# sensor_board.net
KiCad netlist of a schematic drawn in EAGLE
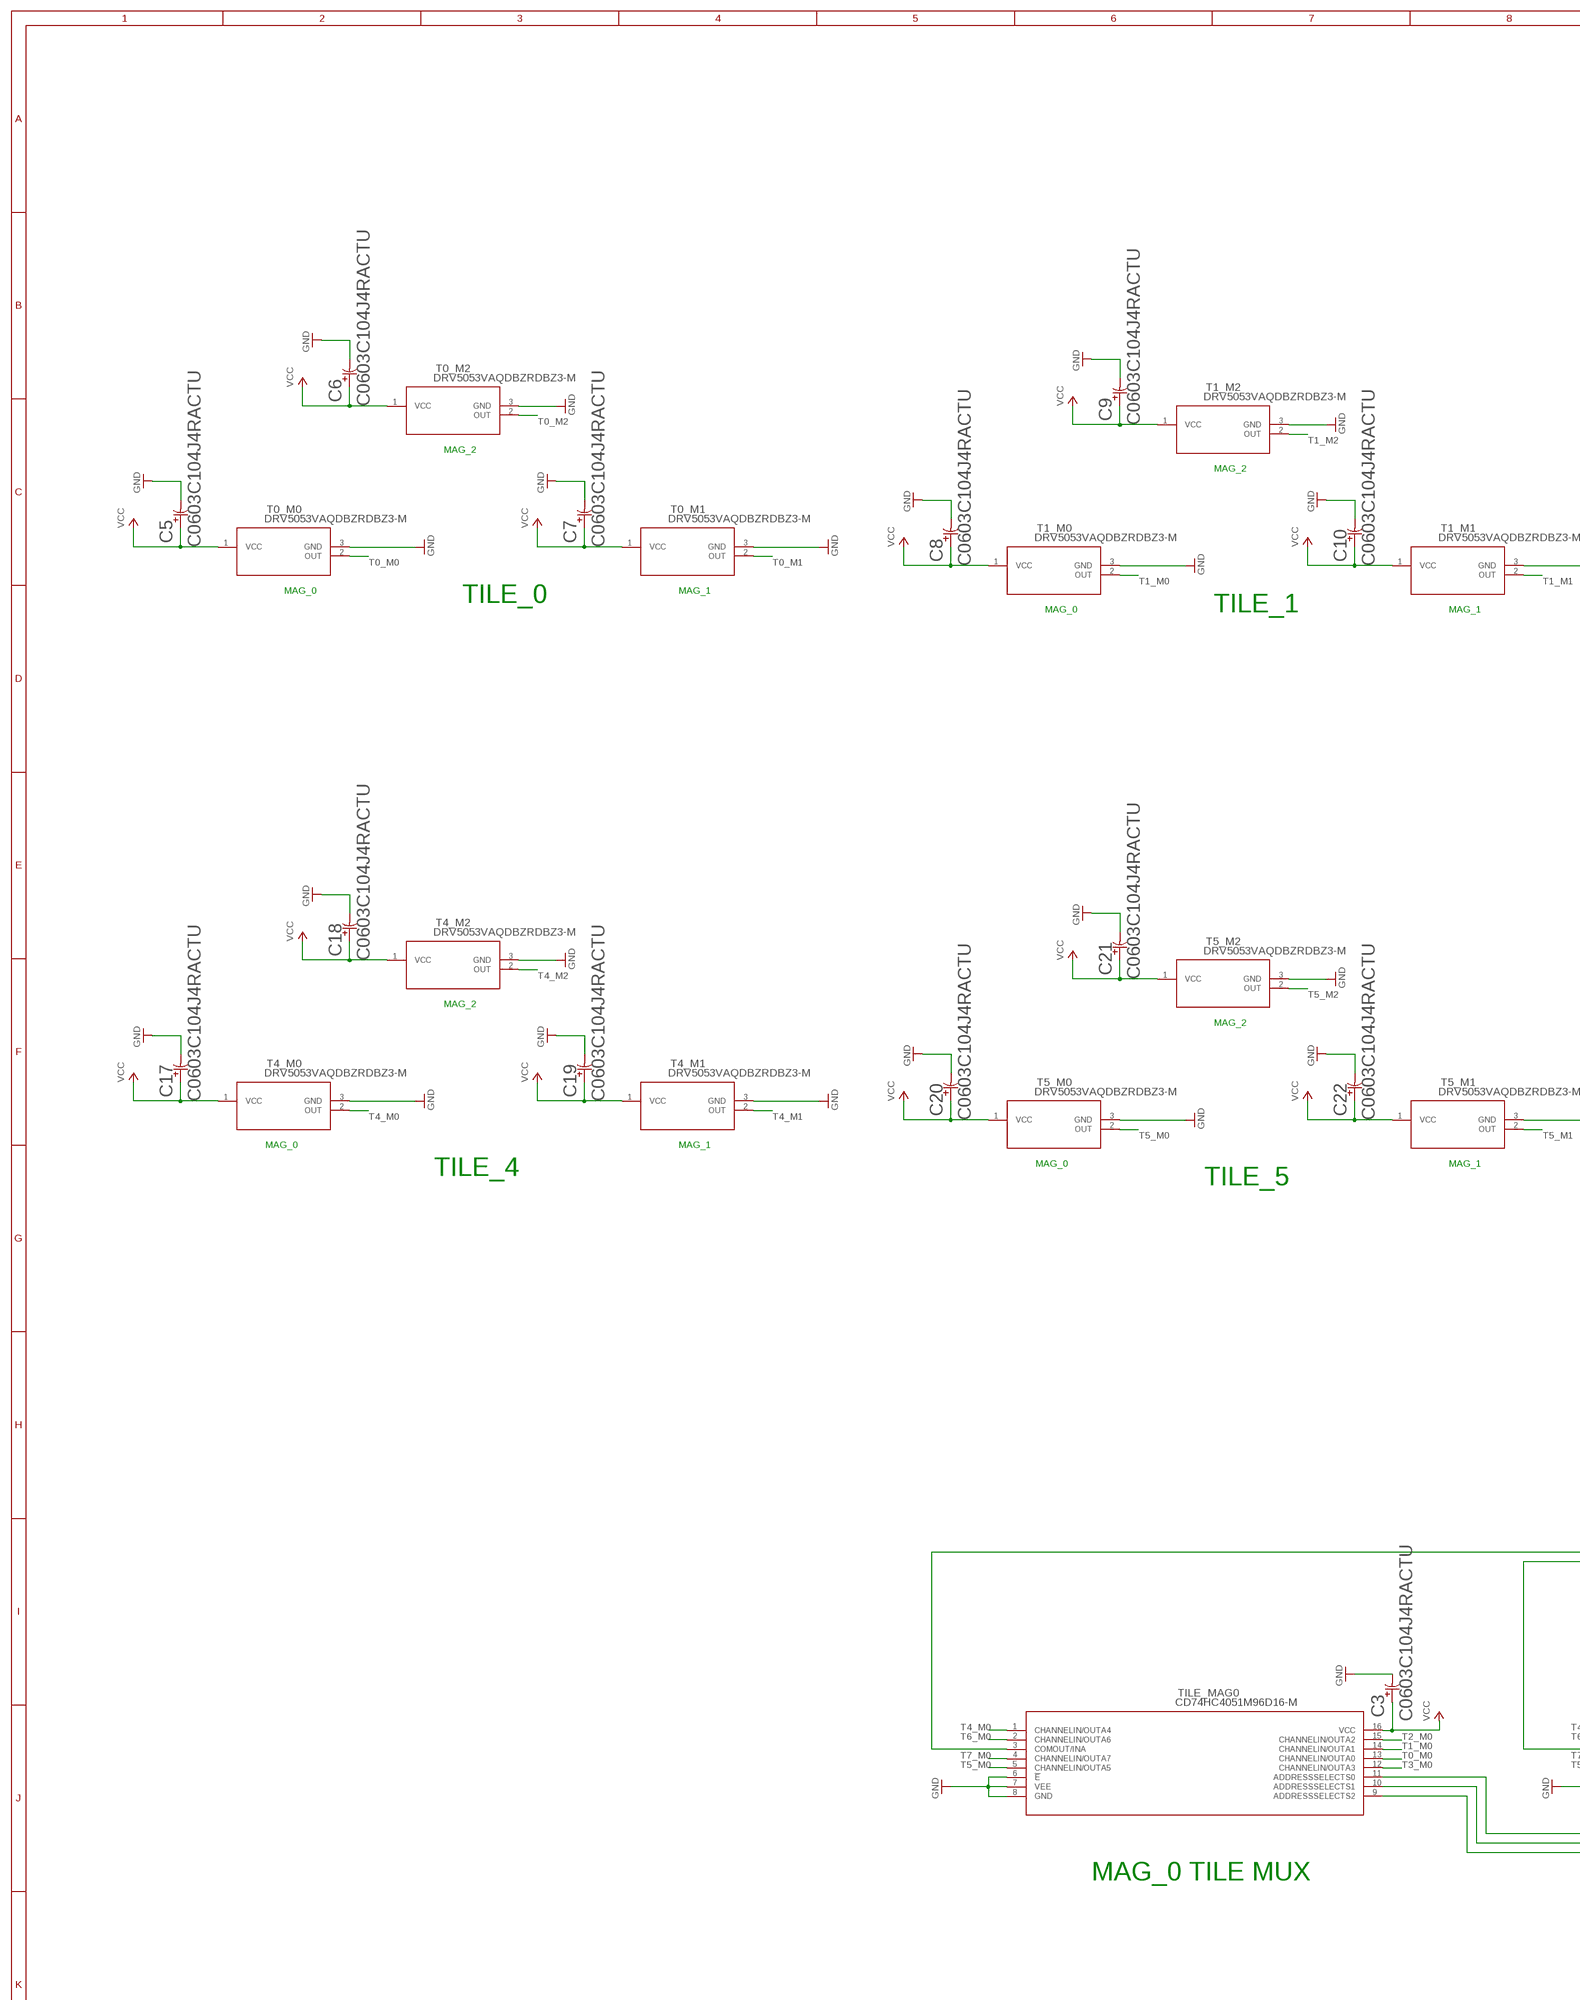
[diagram p0: schematic, sheet 1, part 1 of 3]
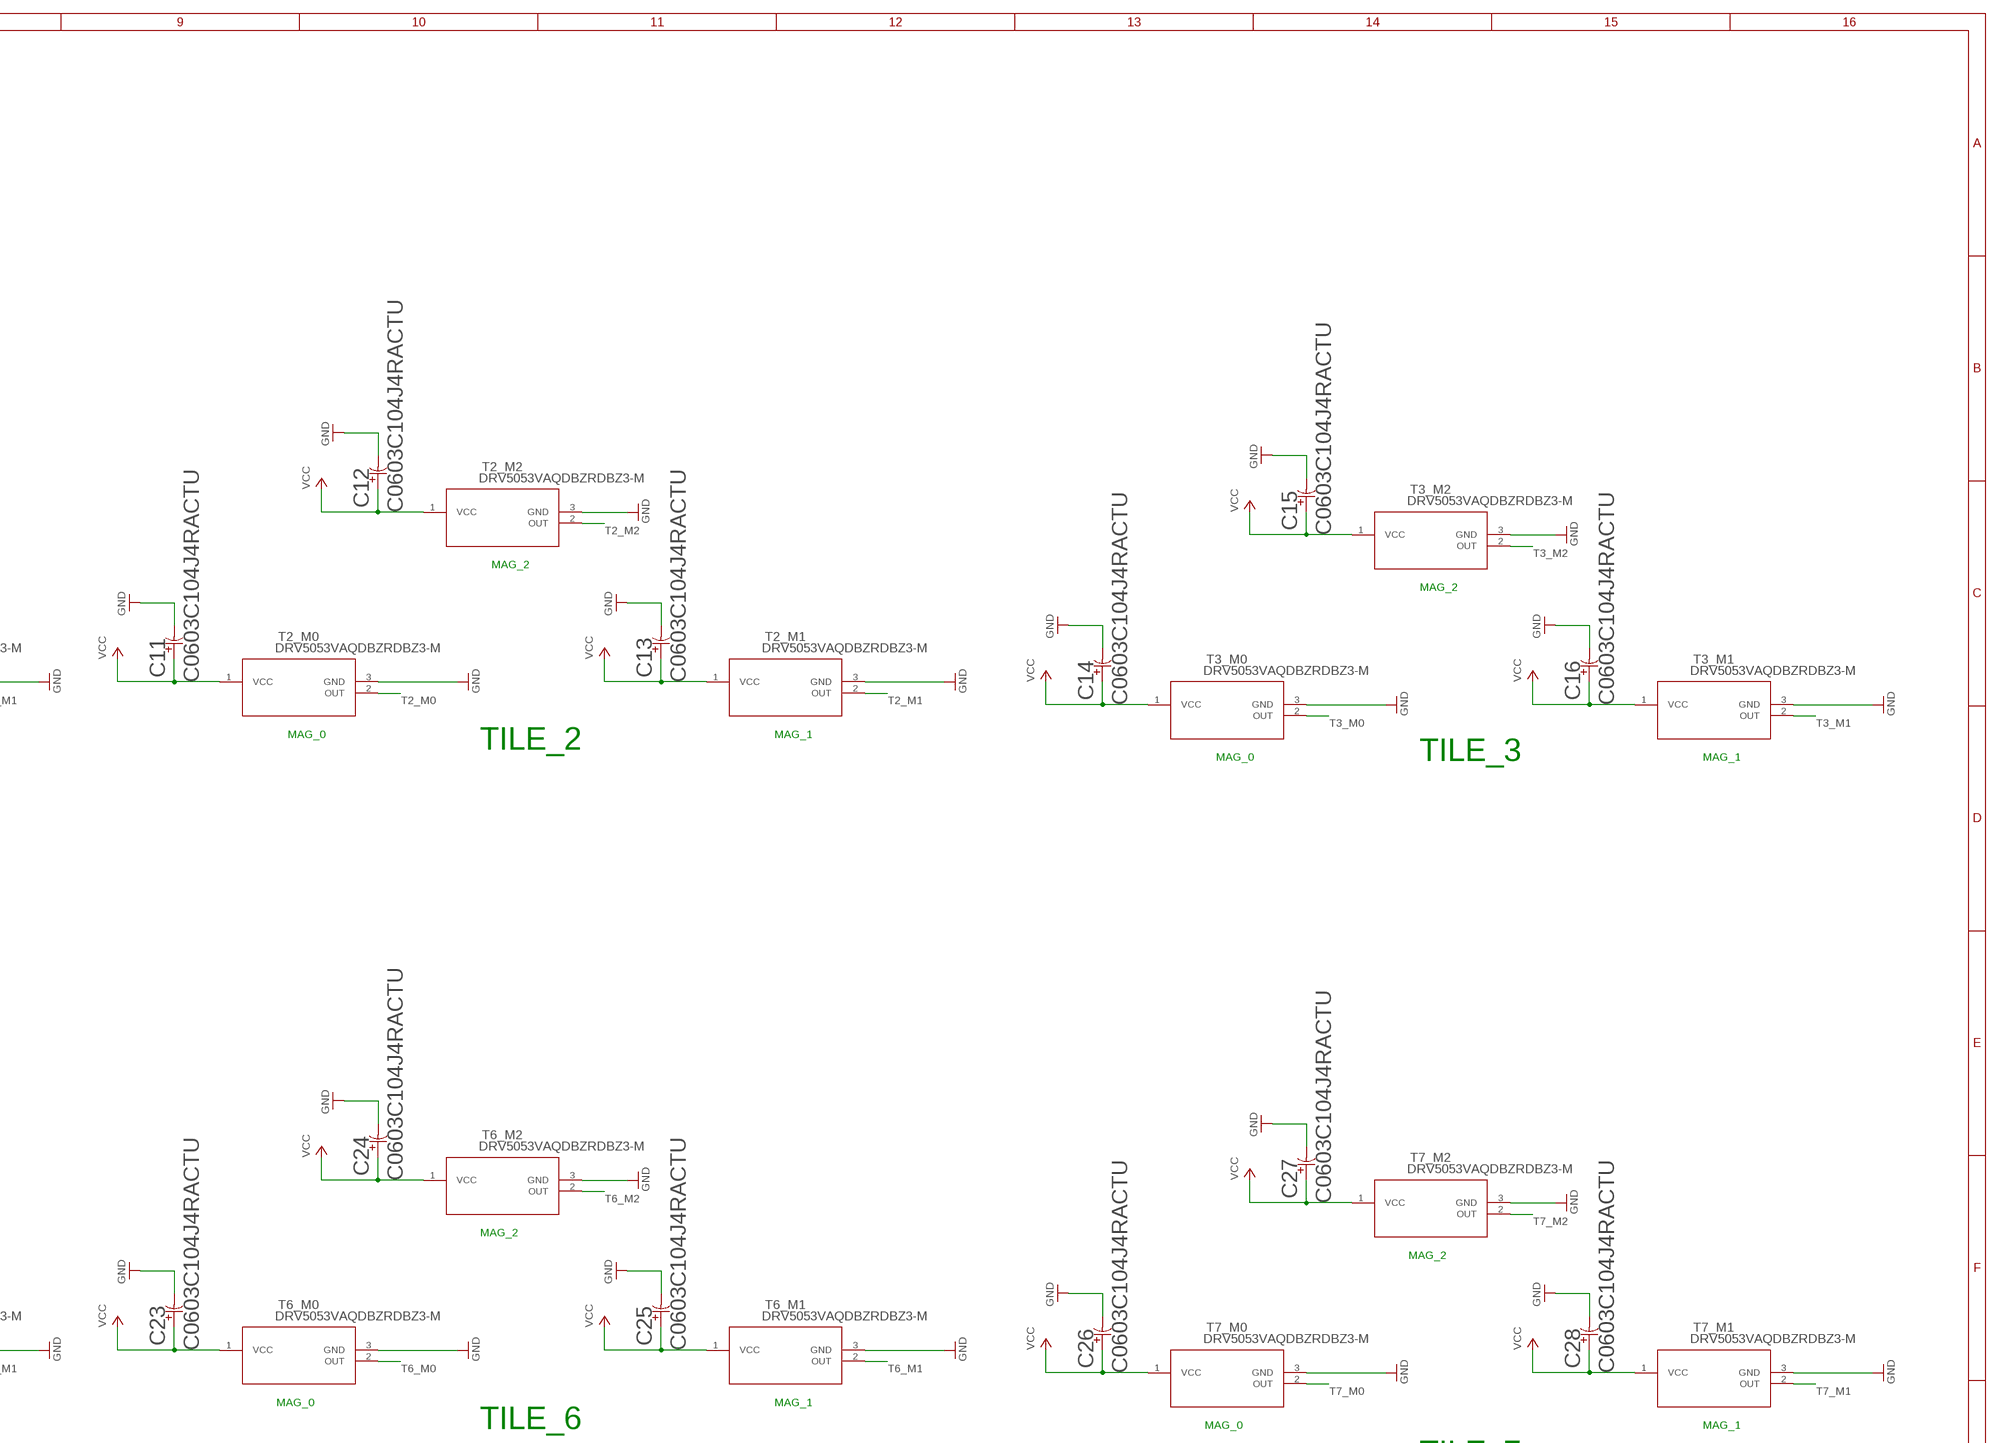
[diagram p1: schematic, sheet 1, part 2 of 3]
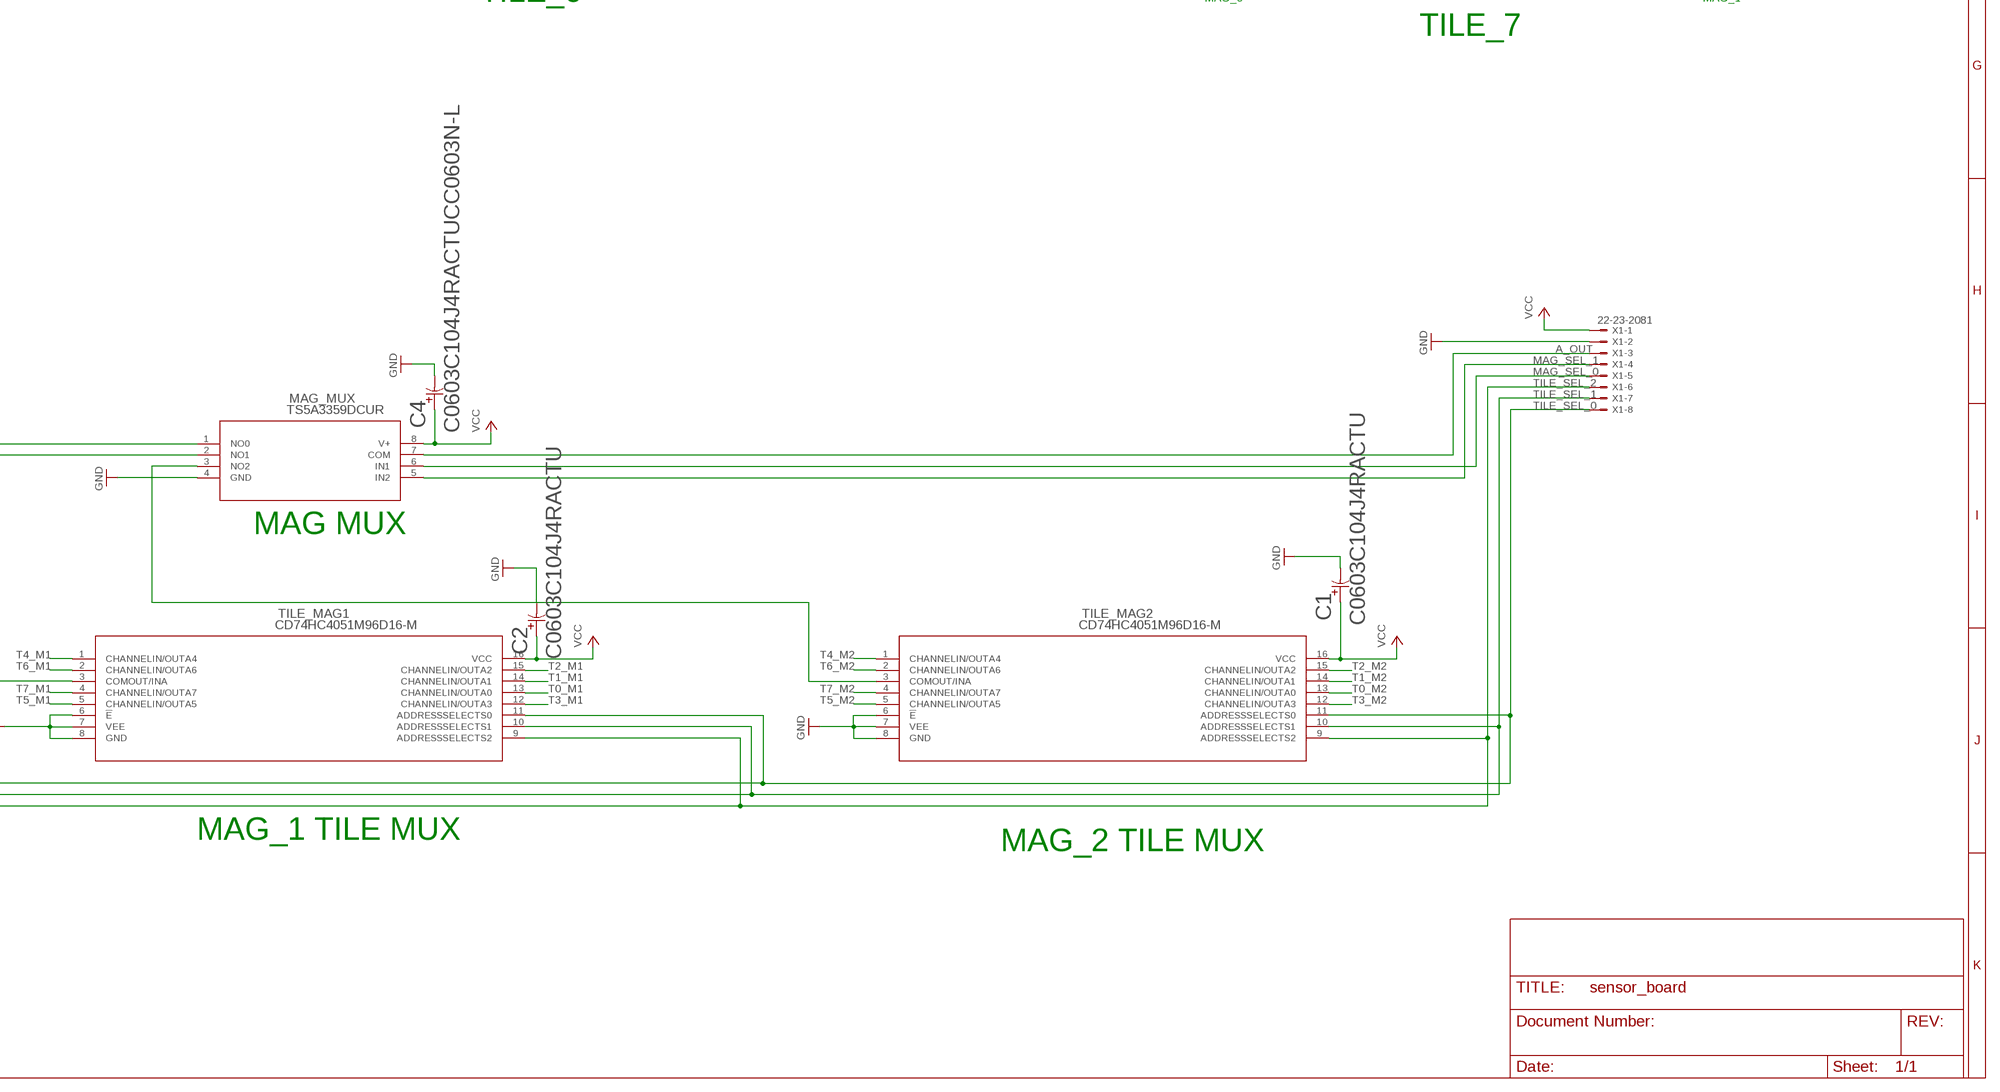
[diagram p2: schematic, sheet 1, part 3 of 3]

(export (version "E")
  (design (tool "Eeschema 10.0.6"))
  (components
    (comp (ref "C1")
      (value "C0603C104J4RACTU")
      (footprint "eagle-import:CC0603N")
      (libsource (lib "eagle-import") (part "C0603C104J4RACTU"))
    )
    (comp (ref "C2")
      (value "C0603C104J4RACTU")
      (footprint "eagle-import:CC0603N")
      (libsource (lib "eagle-import") (part "C0603C104J4RACTU"))
    )
    (comp (ref "C3")
      (value "C0603C104J4RACTU")
      (footprint "eagle-import:CC0603N")
      (libsource (lib "eagle-import") (part "C0603C104J4RACTU"))
    )
    (comp (ref "C4")
      (value "C0603C104J4RACTUCC0603N-L")
      (footprint "eagle-import:CC0603N-L")
      (fields (field (name "MANUFACTURER_PART_NUMBER") "C0603C104J4RACTU"))
      (libsource (lib "eagle-import") (part "C0603C104J4RACTUCC0603N-L"))
    )
    (comp (ref "C5")
      (value "C0603C104J4RACTU")
      (footprint "eagle-import:CC0603N")
      (libsource (lib "eagle-import") (part "C0603C104J4RACTU"))
    )
    (comp (ref "C6")
      (value "C0603C104J4RACTU")
      (footprint "eagle-import:CC0603N")
      (libsource (lib "eagle-import") (part "C0603C104J4RACTU"))
    )
    (comp (ref "C7")
      (value "C0603C104J4RACTU")
      (footprint "eagle-import:CC0603N")
      (libsource (lib "eagle-import") (part "C0603C104J4RACTU"))
    )
    (comp (ref "C8")
      (value "C0603C104J4RACTU")
      (footprint "eagle-import:CC0603N")
      (libsource (lib "eagle-import") (part "C0603C104J4RACTU"))
    )
    (comp (ref "C9")
      (value "C0603C104J4RACTU")
      (footprint "eagle-import:CC0603N")
      (libsource (lib "eagle-import") (part "C0603C104J4RACTU"))
    )
    (comp (ref "C10")
      (value "C0603C104J4RACTU")
      (footprint "eagle-import:CC0603N")
      (libsource (lib "eagle-import") (part "C0603C104J4RACTU"))
    )
    (comp (ref "C11")
      (value "C0603C104J4RACTU")
      (footprint "eagle-import:CC0603N")
      (libsource (lib "eagle-import") (part "C0603C104J4RACTU"))
    )
    (comp (ref "C12")
      (value "C0603C104J4RACTU")
      (footprint "eagle-import:CC0603N")
      (libsource (lib "eagle-import") (part "C0603C104J4RACTU"))
    )
    (comp (ref "C13")
      (value "C0603C104J4RACTU")
      (footprint "eagle-import:CC0603N")
      (libsource (lib "eagle-import") (part "C0603C104J4RACTU"))
    )
    (comp (ref "C14")
      (value "C0603C104J4RACTU")
      (footprint "eagle-import:CC0603N")
      (libsource (lib "eagle-import") (part "C0603C104J4RACTU"))
    )
    (comp (ref "C15")
      (value "C0603C104J4RACTU")
      (footprint "eagle-import:CC0603N")
      (libsource (lib "eagle-import") (part "C0603C104J4RACTU"))
    )
    (comp (ref "C16")
      (value "C0603C104J4RACTU")
      (footprint "eagle-import:CC0603N")
      (libsource (lib "eagle-import") (part "C0603C104J4RACTU"))
    )
    (comp (ref "C17")
      (value "C0603C104J4RACTU")
      (footprint "eagle-import:CC0603N")
      (libsource (lib "eagle-import") (part "C0603C104J4RACTU"))
    )
    (comp (ref "C18")
      (value "C0603C104J4RACTU")
      (footprint "eagle-import:CC0603N")
      (libsource (lib "eagle-import") (part "C0603C104J4RACTU"))
    )
    (comp (ref "C19")
      (value "C0603C104J4RACTU")
      (footprint "eagle-import:CC0603N")
      (libsource (lib "eagle-import") (part "C0603C104J4RACTU"))
    )
    (comp (ref "C20")
      (value "C0603C104J4RACTU")
      (footprint "eagle-import:CC0603N")
      (libsource (lib "eagle-import") (part "C0603C104J4RACTU"))
    )
    (comp (ref "C21")
      (value "C0603C104J4RACTU")
      (footprint "eagle-import:CC0603N")
      (libsource (lib "eagle-import") (part "C0603C104J4RACTU"))
    )
    (comp (ref "C22")
      (value "C0603C104J4RACTU")
      (footprint "eagle-import:CC0603N")
      (libsource (lib "eagle-import") (part "C0603C104J4RACTU"))
    )
    (comp (ref "C23")
      (value "C0603C104J4RACTU")
      (footprint "eagle-import:CC0603N")
      (libsource (lib "eagle-import") (part "C0603C104J4RACTU"))
    )
    (comp (ref "C24")
      (value "C0603C104J4RACTU")
      (footprint "eagle-import:CC0603N")
      (libsource (lib "eagle-import") (part "C0603C104J4RACTU"))
    )
    (comp (ref "C25")
      (value "C0603C104J4RACTU")
      (footprint "eagle-import:CC0603N")
      (libsource (lib "eagle-import") (part "C0603C104J4RACTU"))
    )
    (comp (ref "C26")
      (value "C0603C104J4RACTU")
      (footprint "eagle-import:CC0603N")
      (libsource (lib "eagle-import") (part "C0603C104J4RACTU"))
    )
    (comp (ref "C27")
      (value "C0603C104J4RACTU")
      (footprint "eagle-import:CC0603N")
      (libsource (lib "eagle-import") (part "C0603C104J4RACTU"))
    )
    (comp (ref "C28")
      (value "C0603C104J4RACTU")
      (footprint "eagle-import:CC0603N")
      (libsource (lib "eagle-import") (part "C0603C104J4RACTU"))
    )
    (comp (ref "MAG_MUX")
      (value "TS5A3359DCUR")
      (footprint "eagle-import:DCU8")
      (libsource (lib "eagle-import") (part "TS5A3359DCUR"))
    )
    (comp (ref "T0_M0")
      (value "DRV5053VAQDBZRDBZ3-M")
      (footprint "eagle-import:DBZ3-M")
      (fields (field (name "MANUFACTURER_PART_NUMBER") "drv5053vaqdbzr"))
      (libsource (lib "eagle-import") (part "DRV5053VAQDBZRDBZ3-M"))
    )
    (comp (ref "T0_M1")
      (value "DRV5053VAQDBZRDBZ3-M")
      (footprint "eagle-import:DBZ3-M")
      (fields (field (name "MANUFACTURER_PART_NUMBER") "drv5053vaqdbzr"))
      (libsource (lib "eagle-import") (part "DRV5053VAQDBZRDBZ3-M"))
    )
    (comp (ref "T0_M2")
      (value "DRV5053VAQDBZRDBZ3-M")
      (footprint "eagle-import:DBZ3-M")
      (fields (field (name "MANUFACTURER_PART_NUMBER") "drv5053vaqdbzr"))
      (libsource (lib "eagle-import") (part "DRV5053VAQDBZRDBZ3-M"))
    )
    (comp (ref "T1_M0")
      (value "DRV5053VAQDBZRDBZ3-M")
      (footprint "eagle-import:DBZ3-M")
      (fields (field (name "MANUFACTURER_PART_NUMBER") "drv5053vaqdbzr"))
      (libsource (lib "eagle-import") (part "DRV5053VAQDBZRDBZ3-M"))
    )
    (comp (ref "T1_M1")
      (value "DRV5053VAQDBZRDBZ3-M")
      (footprint "eagle-import:DBZ3-M")
      (fields (field (name "MANUFACTURER_PART_NUMBER") "drv5053vaqdbzr"))
      (libsource (lib "eagle-import") (part "DRV5053VAQDBZRDBZ3-M"))
    )
    (comp (ref "T1_M2")
      (value "DRV5053VAQDBZRDBZ3-M")
      (footprint "eagle-import:DBZ3-M")
      (fields (field (name "MANUFACTURER_PART_NUMBER") "drv5053vaqdbzr"))
      (libsource (lib "eagle-import") (part "DRV5053VAQDBZRDBZ3-M"))
    )
    (comp (ref "T2_M0")
      (value "DRV5053VAQDBZRDBZ3-M")
      (footprint "eagle-import:DBZ3-M")
      (fields (field (name "MANUFACTURER_PART_NUMBER") "drv5053vaqdbzr"))
      (libsource (lib "eagle-import") (part "DRV5053VAQDBZRDBZ3-M"))
    )
    (comp (ref "T2_M1")
      (value "DRV5053VAQDBZRDBZ3-M")
      (footprint "eagle-import:DBZ3-M")
      (fields (field (name "MANUFACTURER_PART_NUMBER") "drv5053vaqdbzr"))
      (libsource (lib "eagle-import") (part "DRV5053VAQDBZRDBZ3-M"))
    )
    (comp (ref "T2_M2")
      (value "DRV5053VAQDBZRDBZ3-M")
      (footprint "eagle-import:DBZ3-M")
      (fields (field (name "MANUFACTURER_PART_NUMBER") "drv5053vaqdbzr"))
      (libsource (lib "eagle-import") (part "DRV5053VAQDBZRDBZ3-M"))
    )
    (comp (ref "T3_M0")
      (value "DRV5053VAQDBZRDBZ3-M")
      (footprint "eagle-import:DBZ3-M")
      (fields (field (name "MANUFACTURER_PART_NUMBER") "drv5053vaqdbzr"))
      (libsource (lib "eagle-import") (part "DRV5053VAQDBZRDBZ3-M"))
    )
    (comp (ref "T3_M1")
      (value "DRV5053VAQDBZRDBZ3-M")
      (footprint "eagle-import:DBZ3-M")
      (fields (field (name "MANUFACTURER_PART_NUMBER") "drv5053vaqdbzr"))
      (libsource (lib "eagle-import") (part "DRV5053VAQDBZRDBZ3-M"))
    )
    (comp (ref "T3_M2")
      (value "DRV5053VAQDBZRDBZ3-M")
      (footprint "eagle-import:DBZ3-M")
      (fields (field (name "MANUFACTURER_PART_NUMBER") "drv5053vaqdbzr"))
      (libsource (lib "eagle-import") (part "DRV5053VAQDBZRDBZ3-M"))
    )
    (comp (ref "T4_M0")
      (value "DRV5053VAQDBZRDBZ3-M")
      (footprint "eagle-import:DBZ3-M")
      (fields (field (name "MANUFACTURER_PART_NUMBER") "drv5053vaqdbzr"))
      (libsource (lib "eagle-import") (part "DRV5053VAQDBZRDBZ3-M"))
    )
    (comp (ref "T4_M1")
      (value "DRV5053VAQDBZRDBZ3-M")
      (footprint "eagle-import:DBZ3-M")
      (fields (field (name "MANUFACTURER_PART_NUMBER") "drv5053vaqdbzr"))
      (libsource (lib "eagle-import") (part "DRV5053VAQDBZRDBZ3-M"))
    )
    (comp (ref "T4_M2")
      (value "DRV5053VAQDBZRDBZ3-M")
      (footprint "eagle-import:DBZ3-M")
      (fields (field (name "MANUFACTURER_PART_NUMBER") "drv5053vaqdbzr"))
      (libsource (lib "eagle-import") (part "DRV5053VAQDBZRDBZ3-M"))
    )
    (comp (ref "T5_M0")
      (value "DRV5053VAQDBZRDBZ3-M")
      (footprint "eagle-import:DBZ3-M")
      (fields (field (name "MANUFACTURER_PART_NUMBER") "drv5053vaqdbzr"))
      (libsource (lib "eagle-import") (part "DRV5053VAQDBZRDBZ3-M"))
    )
    (comp (ref "T5_M1")
      (value "DRV5053VAQDBZRDBZ3-M")
      (footprint "eagle-import:DBZ3-M")
      (fields (field (name "MANUFACTURER_PART_NUMBER") "drv5053vaqdbzr"))
      (libsource (lib "eagle-import") (part "DRV5053VAQDBZRDBZ3-M"))
    )
    (comp (ref "T5_M2")
      (value "DRV5053VAQDBZRDBZ3-M")
      (footprint "eagle-import:DBZ3-M")
      (fields (field (name "MANUFACTURER_PART_NUMBER") "drv5053vaqdbzr"))
      (libsource (lib "eagle-import") (part "DRV5053VAQDBZRDBZ3-M"))
    )
    (comp (ref "T6_M0")
      (value "DRV5053VAQDBZRDBZ3-M")
      (footprint "eagle-import:DBZ3-M")
      (fields (field (name "MANUFACTURER_PART_NUMBER") "drv5053vaqdbzr"))
      (libsource (lib "eagle-import") (part "DRV5053VAQDBZRDBZ3-M"))
    )
    (comp (ref "T6_M1")
      (value "DRV5053VAQDBZRDBZ3-M")
      (footprint "eagle-import:DBZ3-M")
      (fields (field (name "MANUFACTURER_PART_NUMBER") "drv5053vaqdbzr"))
      (libsource (lib "eagle-import") (part "DRV5053VAQDBZRDBZ3-M"))
    )
    (comp (ref "T6_M2")
      (value "DRV5053VAQDBZRDBZ3-M")
      (footprint "eagle-import:DBZ3-M")
      (fields (field (name "MANUFACTURER_PART_NUMBER") "drv5053vaqdbzr"))
      (libsource (lib "eagle-import") (part "DRV5053VAQDBZRDBZ3-M"))
    )
    (comp (ref "T7_M0")
      (value "DRV5053VAQDBZRDBZ3-M")
      (footprint "eagle-import:DBZ3-M")
      (fields (field (name "MANUFACTURER_PART_NUMBER") "drv5053vaqdbzr"))
      (libsource (lib "eagle-import") (part "DRV5053VAQDBZRDBZ3-M"))
    )
    (comp (ref "T7_M1")
      (value "DRV5053VAQDBZRDBZ3-M")
      (footprint "eagle-import:DBZ3-M")
      (fields (field (name "MANUFACTURER_PART_NUMBER") "drv5053vaqdbzr"))
      (libsource (lib "eagle-import") (part "DRV5053VAQDBZRDBZ3-M"))
    )
    (comp (ref "T7_M2")
      (value "DRV5053VAQDBZRDBZ3-M")
      (footprint "eagle-import:DBZ3-M")
      (fields (field (name "MANUFACTURER_PART_NUMBER") "drv5053vaqdbzr"))
      (libsource (lib "eagle-import") (part "DRV5053VAQDBZRDBZ3-M"))
    )
    (comp (ref "TILE_MAG0")
      (value "CD74HC4051M96D16-M")
      (footprint "eagle-import:D16-M")
      (fields (field (name "MANUFACTURER_PART_NUMBER") "CD74HC4051M96"))
      (libsource (lib "eagle-import") (part "CD74HC4051M96D16-M"))
    )
    (comp (ref "TILE_MAG1")
      (value "CD74HC4051M96D16-M")
      (footprint "eagle-import:D16-M")
      (fields (field (name "MANUFACTURER_PART_NUMBER") "CD74HC4051M96"))
      (libsource (lib "eagle-import") (part "CD74HC4051M96D16-M"))
    )
    (comp (ref "TILE_MAG2")
      (value "CD74HC4051M96D16-M")
      (footprint "eagle-import:D16-M")
      (fields (field (name "MANUFACTURER_PART_NUMBER") "CD74HC4051M96"))
      (libsource (lib "eagle-import") (part "CD74HC4051M96D16-M"))
    )
    (comp (ref "X1")
      (value "22-23-2081")
      (footprint "eagle-import:22-23-2081")
      (fields (field (name "MF") "MOLEX"))
      (libsource (lib "eagle-import") (part "22-23-2081"))
    )
  )
  (nets
    (net (code "1") (name "/A_OUT") (class "Default")
      (node (ref "MAG_MUX") (pin "7") (pinfunction "COM_7") (pintype "passive"))
      (node (ref "X1") (pin "3") (pinfunction "S_3") (pintype "passive"))
    )
    (net (code "2") (name "/MAG_SEL_0") (class "Default")
      (node (ref "MAG_MUX") (pin "6") (pinfunction "IN1_6") (pintype "input"))
      (node (ref "X1") (pin "5") (pinfunction "S_5") (pintype "passive"))
    )
    (net (code "3") (name "/MAG_SEL_1") (class "Default")
      (node (ref "MAG_MUX") (pin "5") (pinfunction "IN2_5") (pintype "input"))
      (node (ref "X1") (pin "4") (pinfunction "S_4") (pintype "passive"))
    )
    (net (code "4") (name "/T0_M0") (class "Default")
      (node (ref "T0_M0") (pin "2") (pinfunction "OUT_2") (pintype "output"))
      (node (ref "TILE_MAG0") (pin "13") (pinfunction "CHANNELIN/OUTA0_13") (pintype "bidirectional"))
    )
    (net (code "5") (name "/T0_M1") (class "Default")
      (node (ref "T0_M1") (pin "2") (pinfunction "OUT_2") (pintype "output"))
      (node (ref "TILE_MAG1") (pin "13") (pinfunction "CHANNELIN/OUTA0_13") (pintype "bidirectional"))
    )
    (net (code "6") (name "/T0_M2") (class "Default")
      (node (ref "T0_M2") (pin "2") (pinfunction "OUT_2") (pintype "output"))
      (node (ref "TILE_MAG2") (pin "13") (pinfunction "CHANNELIN/OUTA0_13") (pintype "bidirectional"))
    )
    (net (code "7") (name "/T1_M0") (class "Default")
      (node (ref "T1_M0") (pin "2") (pinfunction "OUT_2") (pintype "output"))
      (node (ref "TILE_MAG0") (pin "14") (pinfunction "CHANNELIN/OUTA1_14") (pintype "bidirectional"))
    )
    (net (code "8") (name "/T1_M1") (class "Default")
      (node (ref "T1_M1") (pin "2") (pinfunction "OUT_2") (pintype "output"))
      (node (ref "TILE_MAG1") (pin "14") (pinfunction "CHANNELIN/OUTA1_14") (pintype "bidirectional"))
    )
    (net (code "9") (name "/T1_M2") (class "Default")
      (node (ref "T1_M2") (pin "2") (pinfunction "OUT_2") (pintype "output"))
      (node (ref "TILE_MAG2") (pin "14") (pinfunction "CHANNELIN/OUTA1_14") (pintype "bidirectional"))
    )
    (net (code "10") (name "/T2_M0") (class "Default")
      (node (ref "T2_M0") (pin "2") (pinfunction "OUT_2") (pintype "output"))
      (node (ref "TILE_MAG0") (pin "15") (pinfunction "CHANNELIN/OUTA2_15") (pintype "bidirectional"))
    )
    (net (code "11") (name "/T2_M1") (class "Default")
      (node (ref "T2_M1") (pin "2") (pinfunction "OUT_2") (pintype "output"))
      (node (ref "TILE_MAG1") (pin "15") (pinfunction "CHANNELIN/OUTA2_15") (pintype "bidirectional"))
    )
    (net (code "12") (name "/T2_M2") (class "Default")
      (node (ref "T2_M2") (pin "2") (pinfunction "OUT_2") (pintype "output"))
      (node (ref "TILE_MAG2") (pin "15") (pinfunction "CHANNELIN/OUTA2_15") (pintype "bidirectional"))
    )
    (net (code "13") (name "/T3_M0") (class "Default")
      (node (ref "T3_M0") (pin "2") (pinfunction "OUT_2") (pintype "output"))
      (node (ref "TILE_MAG0") (pin "12") (pinfunction "CHANNELIN/OUTA3_12") (pintype "bidirectional"))
    )
    (net (code "14") (name "/T3_M1") (class "Default")
      (node (ref "T3_M1") (pin "2") (pinfunction "OUT_2") (pintype "output"))
      (node (ref "TILE_MAG1") (pin "12") (pinfunction "CHANNELIN/OUTA3_12") (pintype "bidirectional"))
    )
    (net (code "15") (name "/T3_M2") (class "Default")
      (node (ref "T3_M2") (pin "2") (pinfunction "OUT_2") (pintype "output"))
      (node (ref "TILE_MAG2") (pin "12") (pinfunction "CHANNELIN/OUTA3_12") (pintype "bidirectional"))
    )
    (net (code "16") (name "/T4_M0") (class "Default")
      (node (ref "T4_M0") (pin "2") (pinfunction "OUT_2") (pintype "output"))
      (node (ref "TILE_MAG0") (pin "1") (pinfunction "CHANNELIN/OUTA4_1") (pintype "bidirectional"))
    )
    (net (code "17") (name "/T4_M1") (class "Default")
      (node (ref "T4_M1") (pin "2") (pinfunction "OUT_2") (pintype "output"))
      (node (ref "TILE_MAG1") (pin "1") (pinfunction "CHANNELIN/OUTA4_1") (pintype "bidirectional"))
    )
    (net (code "18") (name "/T4_M2") (class "Default")
      (node (ref "T4_M2") (pin "2") (pinfunction "OUT_2") (pintype "output"))
      (node (ref "TILE_MAG2") (pin "1") (pinfunction "CHANNELIN/OUTA4_1") (pintype "bidirectional"))
    )
    (net (code "19") (name "/T5_M0") (class "Default")
      (node (ref "T5_M0") (pin "2") (pinfunction "OUT_2") (pintype "output"))
      (node (ref "TILE_MAG0") (pin "5") (pinfunction "CHANNELIN/OUTA5_5") (pintype "bidirectional"))
    )
    (net (code "20") (name "/T5_M1") (class "Default")
      (node (ref "T5_M1") (pin "2") (pinfunction "OUT_2") (pintype "output"))
      (node (ref "TILE_MAG1") (pin "5") (pinfunction "CHANNELIN/OUTA5_5") (pintype "bidirectional"))
    )
    (net (code "21") (name "/T5_M2") (class "Default")
      (node (ref "T5_M2") (pin "2") (pinfunction "OUT_2") (pintype "output"))
      (node (ref "TILE_MAG2") (pin "5") (pinfunction "CHANNELIN/OUTA5_5") (pintype "bidirectional"))
    )
    (net (code "22") (name "/T6_M0") (class "Default")
      (node (ref "T6_M0") (pin "2") (pinfunction "OUT_2") (pintype "output"))
      (node (ref "TILE_MAG0") (pin "2") (pinfunction "CHANNELIN/OUTA6_2") (pintype "bidirectional"))
    )
    (net (code "23") (name "/T6_M1") (class "Default")
      (node (ref "T6_M1") (pin "2") (pinfunction "OUT_2") (pintype "output"))
      (node (ref "TILE_MAG1") (pin "2") (pinfunction "CHANNELIN/OUTA6_2") (pintype "bidirectional"))
    )
    (net (code "24") (name "/T6_M2") (class "Default")
      (node (ref "T6_M2") (pin "2") (pinfunction "OUT_2") (pintype "output"))
      (node (ref "TILE_MAG2") (pin "2") (pinfunction "CHANNELIN/OUTA6_2") (pintype "bidirectional"))
    )
    (net (code "25") (name "/T7_M0") (class "Default")
      (node (ref "T7_M0") (pin "2") (pinfunction "OUT_2") (pintype "output"))
      (node (ref "TILE_MAG0") (pin "4") (pinfunction "CHANNELIN/OUTA7_4") (pintype "bidirectional"))
    )
    (net (code "26") (name "/T7_M1") (class "Default")
      (node (ref "T7_M1") (pin "2") (pinfunction "OUT_2") (pintype "output"))
      (node (ref "TILE_MAG1") (pin "4") (pinfunction "CHANNELIN/OUTA7_4") (pintype "bidirectional"))
    )
    (net (code "27") (name "/T7_M2") (class "Default")
      (node (ref "T7_M2") (pin "2") (pinfunction "OUT_2") (pintype "output"))
      (node (ref "TILE_MAG2") (pin "4") (pinfunction "CHANNELIN/OUTA7_4") (pintype "bidirectional"))
    )
    (net (code "28") (name "/TILE_SEL_0") (class "Default")
      (node (ref "TILE_MAG0") (pin "11") (pinfunction "ADDRESSSELECTS0_11") (pintype "input"))
      (node (ref "TILE_MAG1") (pin "11") (pinfunction "ADDRESSSELECTS0_11") (pintype "input"))
      (node (ref "TILE_MAG2") (pin "11") (pinfunction "ADDRESSSELECTS0_11") (pintype "input"))
      (node (ref "X1") (pin "8") (pinfunction "S_8") (pintype "passive"))
    )
    (net (code "29") (name "/TILE_SEL_1") (class "Default")
      (node (ref "TILE_MAG0") (pin "10") (pinfunction "ADDRESSSELECTS1_10") (pintype "input"))
      (node (ref "TILE_MAG1") (pin "10") (pinfunction "ADDRESSSELECTS1_10") (pintype "input"))
      (node (ref "TILE_MAG2") (pin "10") (pinfunction "ADDRESSSELECTS1_10") (pintype "input"))
      (node (ref "X1") (pin "7") (pinfunction "S_7") (pintype "passive"))
    )
    (net (code "30") (name "/TILE_SEL_2") (class "Default")
      (node (ref "TILE_MAG0") (pin "9") (pinfunction "ADDRESSSELECTS2_9") (pintype "input"))
      (node (ref "TILE_MAG1") (pin "9") (pinfunction "ADDRESSSELECTS2_9") (pintype "input"))
      (node (ref "TILE_MAG2") (pin "9") (pinfunction "ADDRESSSELECTS2_9") (pintype "input"))
      (node (ref "X1") (pin "6") (pinfunction "S_6") (pintype "passive"))
    )
    (net (code "31") (name "GND") (class "Default")
      (node (ref "C1") (pin "2") (pinfunction "22_2") (pintype "passive"))
      (node (ref "C10") (pin "2") (pinfunction "22_2") (pintype "passive"))
      (node (ref "C11") (pin "2") (pinfunction "22_2") (pintype "passive"))
      (node (ref "C12") (pin "2") (pinfunction "22_2") (pintype "passive"))
      (node (ref "C13") (pin "2") (pinfunction "22_2") (pintype "passive"))
      (node (ref "C14") (pin "2") (pinfunction "22_2") (pintype "passive"))
      (node (ref "C15") (pin "2") (pinfunction "22_2") (pintype "passive"))
      (node (ref "C16") (pin "2") (pinfunction "22_2") (pintype "passive"))
      (node (ref "C17") (pin "2") (pinfunction "22_2") (pintype "passive"))
      (node (ref "C18") (pin "2") (pinfunction "22_2") (pintype "passive"))
      (node (ref "C19") (pin "2") (pinfunction "22_2") (pintype "passive"))
      (node (ref "C2") (pin "2") (pinfunction "22_2") (pintype "passive"))
      (node (ref "C20") (pin "2") (pinfunction "22_2") (pintype "passive"))
      (node (ref "C21") (pin "2") (pinfunction "22_2") (pintype "passive"))
      (node (ref "C22") (pin "2") (pinfunction "22_2") (pintype "passive"))
      (node (ref "C23") (pin "2") (pinfunction "22_2") (pintype "passive"))
      (node (ref "C24") (pin "2") (pinfunction "22_2") (pintype "passive"))
      (node (ref "C25") (pin "2") (pinfunction "22_2") (pintype "passive"))
      (node (ref "C26") (pin "2") (pinfunction "22_2") (pintype "passive"))
      (node (ref "C27") (pin "2") (pinfunction "22_2") (pintype "passive"))
      (node (ref "C28") (pin "2") (pinfunction "22_2") (pintype "passive"))
      (node (ref "C3") (pin "2") (pinfunction "22_2") (pintype "passive"))
      (node (ref "C4") (pin "2") (pinfunction "22_2") (pintype "passive"))
      (node (ref "C5") (pin "2") (pinfunction "22_2") (pintype "passive"))
      (node (ref "C6") (pin "2") (pinfunction "22_2") (pintype "passive"))
      (node (ref "C7") (pin "2") (pinfunction "22_2") (pintype "passive"))
      (node (ref "C8") (pin "2") (pinfunction "22_2") (pintype "passive"))
      (node (ref "C9") (pin "2") (pinfunction "22_2") (pintype "passive"))
      (node (ref "MAG_MUX") (pin "4") (pinfunction "GND_4") (pintype "power_in"))
      (node (ref "T0_M0") (pin "3") (pinfunction "GND_3") (pintype "power_in"))
      (node (ref "T0_M1") (pin "3") (pinfunction "GND_3") (pintype "power_in"))
      (node (ref "T0_M2") (pin "3") (pinfunction "GND_3") (pintype "power_in"))
      (node (ref "T1_M0") (pin "3") (pinfunction "GND_3") (pintype "power_in"))
      (node (ref "T1_M1") (pin "3") (pinfunction "GND_3") (pintype "power_in"))
      (node (ref "T1_M2") (pin "3") (pinfunction "GND_3") (pintype "power_in"))
      (node (ref "T2_M0") (pin "3") (pinfunction "GND_3") (pintype "power_in"))
      (node (ref "T2_M1") (pin "3") (pinfunction "GND_3") (pintype "power_in"))
      (node (ref "T2_M2") (pin "3") (pinfunction "GND_3") (pintype "power_in"))
      (node (ref "T3_M0") (pin "3") (pinfunction "GND_3") (pintype "power_in"))
      (node (ref "T3_M1") (pin "3") (pinfunction "GND_3") (pintype "power_in"))
      (node (ref "T3_M2") (pin "3") (pinfunction "GND_3") (pintype "power_in"))
      (node (ref "T4_M0") (pin "3") (pinfunction "GND_3") (pintype "power_in"))
      (node (ref "T4_M1") (pin "3") (pinfunction "GND_3") (pintype "power_in"))
      (node (ref "T4_M2") (pin "3") (pinfunction "GND_3") (pintype "power_in"))
      (node (ref "T5_M0") (pin "3") (pinfunction "GND_3") (pintype "power_in"))
      (node (ref "T5_M1") (pin "3") (pinfunction "GND_3") (pintype "power_in"))
      (node (ref "T5_M2") (pin "3") (pinfunction "GND_3") (pintype "power_in"))
      (node (ref "T6_M0") (pin "3") (pinfunction "GND_3") (pintype "power_in"))
      (node (ref "T6_M1") (pin "3") (pinfunction "GND_3") (pintype "power_in"))
      (node (ref "T6_M2") (pin "3") (pinfunction "GND_3") (pintype "power_in"))
      (node (ref "T7_M0") (pin "3") (pinfunction "GND_3") (pintype "power_in"))
      (node (ref "T7_M1") (pin "3") (pinfunction "GND_3") (pintype "power_in"))
      (node (ref "T7_M2") (pin "3") (pinfunction "GND_3") (pintype "power_in"))
      (node (ref "TILE_MAG0") (pin "6") (pinfunction "~{E}_6") (pintype "input"))
      (node (ref "TILE_MAG0") (pin "7") (pinfunction "VEE_7") (pintype "power_in"))
      (node (ref "TILE_MAG0") (pin "8") (pinfunction "GND_8") (pintype "power_in"))
      (node (ref "TILE_MAG1") (pin "6") (pinfunction "~{E}_6") (pintype "input"))
      (node (ref "TILE_MAG1") (pin "7") (pinfunction "VEE_7") (pintype "power_in"))
      (node (ref "TILE_MAG1") (pin "8") (pinfunction "GND_8") (pintype "power_in"))
      (node (ref "TILE_MAG2") (pin "6") (pinfunction "~{E}_6") (pintype "input"))
      (node (ref "TILE_MAG2") (pin "7") (pinfunction "VEE_7") (pintype "power_in"))
      (node (ref "TILE_MAG2") (pin "8") (pinfunction "GND_8") (pintype "power_in"))
      (node (ref "X1") (pin "2") (pinfunction "S_2") (pintype "passive"))
    )
    (net (code "32") (name "Net-(MAG_MUX-NO0)") (class "Default")
      (node (ref "MAG_MUX") (pin "1") (pinfunction "NO0_1") (pintype "output"))
      (node (ref "TILE_MAG0") (pin "3") (pinfunction "COMOUT/INA_3") (pintype "bidirectional"))
    )
    (net (code "33") (name "Net-(MAG_MUX-NO1)") (class "Default")
      (node (ref "MAG_MUX") (pin "2") (pinfunction "NO1_2") (pintype "output"))
      (node (ref "TILE_MAG1") (pin "3") (pinfunction "COMOUT/INA_3") (pintype "bidirectional"))
    )
    (net (code "34") (name "Net-(MAG_MUX-NO2)") (class "Default")
      (node (ref "MAG_MUX") (pin "3") (pinfunction "NO2_3") (pintype "output"))
      (node (ref "TILE_MAG2") (pin "3") (pinfunction "COMOUT/INA_3") (pintype "bidirectional"))
    )
    (net (code "35") (name "VCC") (class "Default")
      (node (ref "C1") (pin "1") (pinfunction "11_1") (pintype "passive"))
      (node (ref "C10") (pin "1") (pinfunction "11_1") (pintype "passive"))
      (node (ref "C11") (pin "1") (pinfunction "11_1") (pintype "passive"))
      (node (ref "C12") (pin "1") (pinfunction "11_1") (pintype "passive"))
      (node (ref "C13") (pin "1") (pinfunction "11_1") (pintype "passive"))
      (node (ref "C14") (pin "1") (pinfunction "11_1") (pintype "passive"))
      (node (ref "C15") (pin "1") (pinfunction "11_1") (pintype "passive"))
      (node (ref "C16") (pin "1") (pinfunction "11_1") (pintype "passive"))
      (node (ref "C17") (pin "1") (pinfunction "11_1") (pintype "passive"))
      (node (ref "C18") (pin "1") (pinfunction "11_1") (pintype "passive"))
      (node (ref "C19") (pin "1") (pinfunction "11_1") (pintype "passive"))
      (node (ref "C2") (pin "1") (pinfunction "11_1") (pintype "passive"))
      (node (ref "C20") (pin "1") (pinfunction "11_1") (pintype "passive"))
      (node (ref "C21") (pin "1") (pinfunction "11_1") (pintype "passive"))
      (node (ref "C22") (pin "1") (pinfunction "11_1") (pintype "passive"))
      (node (ref "C23") (pin "1") (pinfunction "11_1") (pintype "passive"))
      (node (ref "C24") (pin "1") (pinfunction "11_1") (pintype "passive"))
      (node (ref "C25") (pin "1") (pinfunction "11_1") (pintype "passive"))
      (node (ref "C26") (pin "1") (pinfunction "11_1") (pintype "passive"))
      (node (ref "C27") (pin "1") (pinfunction "11_1") (pintype "passive"))
      (node (ref "C28") (pin "1") (pinfunction "11_1") (pintype "passive"))
      (node (ref "C3") (pin "1") (pinfunction "11_1") (pintype "passive"))
      (node (ref "C4") (pin "1") (pinfunction "11_1") (pintype "passive"))
      (node (ref "C5") (pin "1") (pinfunction "11_1") (pintype "passive"))
      (node (ref "C6") (pin "1") (pinfunction "11_1") (pintype "passive"))
      (node (ref "C7") (pin "1") (pinfunction "11_1") (pintype "passive"))
      (node (ref "C8") (pin "1") (pinfunction "11_1") (pintype "passive"))
      (node (ref "C9") (pin "1") (pinfunction "11_1") (pintype "passive"))
      (node (ref "MAG_MUX") (pin "8") (pinfunction "V+_8") (pintype "power_in"))
      (node (ref "T0_M0") (pin "1") (pinfunction "VCC_1") (pintype "power_in"))
      (node (ref "T0_M1") (pin "1") (pinfunction "VCC_1") (pintype "power_in"))
      (node (ref "T0_M2") (pin "1") (pinfunction "VCC_1") (pintype "power_in"))
      (node (ref "T1_M0") (pin "1") (pinfunction "VCC_1") (pintype "power_in"))
      (node (ref "T1_M1") (pin "1") (pinfunction "VCC_1") (pintype "power_in"))
      (node (ref "T1_M2") (pin "1") (pinfunction "VCC_1") (pintype "power_in"))
      (node (ref "T2_M0") (pin "1") (pinfunction "VCC_1") (pintype "power_in"))
      (node (ref "T2_M1") (pin "1") (pinfunction "VCC_1") (pintype "power_in"))
      (node (ref "T2_M2") (pin "1") (pinfunction "VCC_1") (pintype "power_in"))
      (node (ref "T3_M0") (pin "1") (pinfunction "VCC_1") (pintype "power_in"))
      (node (ref "T3_M1") (pin "1") (pinfunction "VCC_1") (pintype "power_in"))
      (node (ref "T3_M2") (pin "1") (pinfunction "VCC_1") (pintype "power_in"))
      (node (ref "T4_M0") (pin "1") (pinfunction "VCC_1") (pintype "power_in"))
      (node (ref "T4_M1") (pin "1") (pinfunction "VCC_1") (pintype "power_in"))
      (node (ref "T4_M2") (pin "1") (pinfunction "VCC_1") (pintype "power_in"))
      (node (ref "T5_M0") (pin "1") (pinfunction "VCC_1") (pintype "power_in"))
      (node (ref "T5_M1") (pin "1") (pinfunction "VCC_1") (pintype "power_in"))
      (node (ref "T5_M2") (pin "1") (pinfunction "VCC_1") (pintype "power_in"))
      (node (ref "T6_M0") (pin "1") (pinfunction "VCC_1") (pintype "power_in"))
      (node (ref "T6_M1") (pin "1") (pinfunction "VCC_1") (pintype "power_in"))
      (node (ref "T6_M2") (pin "1") (pinfunction "VCC_1") (pintype "power_in"))
      (node (ref "T7_M0") (pin "1") (pinfunction "VCC_1") (pintype "power_in"))
      (node (ref "T7_M1") (pin "1") (pinfunction "VCC_1") (pintype "power_in"))
      (node (ref "T7_M2") (pin "1") (pinfunction "VCC_1") (pintype "power_in"))
      (node (ref "TILE_MAG0") (pin "16") (pinfunction "VCC_16") (pintype "power_in"))
      (node (ref "TILE_MAG1") (pin "16") (pinfunction "VCC_16") (pintype "power_in"))
      (node (ref "TILE_MAG2") (pin "16") (pinfunction "VCC_16") (pintype "power_in"))
      (node (ref "X1") (pin "1") (pinfunction "S_1") (pintype "passive"))
    )
  )
)
